# Power_supply_dual_-_2_5_V_250_mA_-_TI_LM.net
KiCad netlist of a schematic drawn in Altium Designer
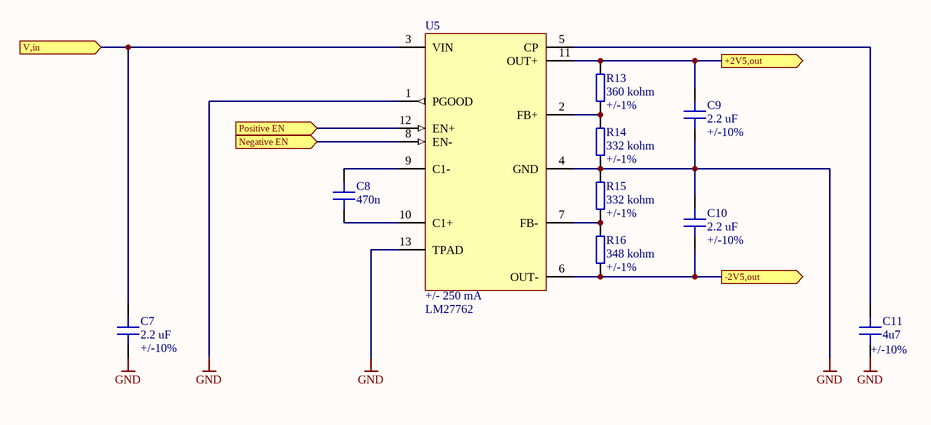
[diagram p0: Power supply, dual - 2.5 V 250 mA - TI LM27762.SchDoc]

(export (version "E")
  (design (tool "Eeschema 10.0.6"))
  (components
    (comp (ref "C7")
      (value "2.2 uF")
      (footprint "Capacitor 0805 [2012 Metric]; SMT")
      (fields
        (field (name "TOLERANCE") "+/-10%")
        (field (name "PART NUMBER") "GRM21BR61H225KA73L")
        (field (name "Comment") "Capacitor")
        (field (name "AUTHOR") "Jeroen de Bruijn")
      )
      (libsource (lib "VidavidorraDb") (part "Capacitor"))
    )
    (comp (ref "C8")
      (value "470n")
      (footprint "Capacitor 0805 [2012 Metric]; SMT")
      (fields (field (name "Comment") "Capacitor") (field (name "AUTHOR") "Jeroen de Bruijn"))
      (libsource (lib "VidavidorraDb") (part "Capacitor"))
    )
    (comp (ref "C9")
      (value "2.2 uF")
      (footprint "Capacitor 0805 [2012 Metric]; SMT")
      (fields
        (field (name "TOLERANCE") "+/-10%")
        (field (name "PART NUMBER") "GRM21BR61H225KA73L")
        (field (name "Comment") "Capacitor")
        (field (name "AUTHOR") "Jeroen de Bruijn")
      )
      (libsource (lib "VidavidorraDb") (part "Capacitor"))
    )
    (comp (ref "C10")
      (value "2.2 uF")
      (footprint "Capacitor 0805 [2012 Metric]; SMT")
      (fields
        (field (name "TOLERANCE") "+/-10%")
        (field (name "PART NUMBER") "GRM21BR61H225KA73L")
        (field (name "Comment") "Capacitor")
        (field (name "AUTHOR") "Jeroen de Bruijn")
      )
      (libsource (lib "VidavidorraDb") (part "Capacitor"))
    )
    (comp (ref "C11")
      (value "4u7")
      (footprint "Capacitor 0805 [2012 Metric]; SMT")
      (fields
        (field (name "TOLERANCE") "+/-10%")
        (field (name "PART NUMBER") "0805B475K160CT")
        (field (name "Comment") "Capacitor")
        (field (name "AUTHOR") "Jeroen de Bruijn")
      )
      (libsource (lib "VidavidorraDb") (part "Capacitor"))
    )
    (comp (ref "R13")
      (value "360 kohm")
      (footprint "Resistor 0805 [2012 Metric]; SMT")
      (fields
        (field (name "TOLERANCE") "+/-1%")
        (field (name "PART NUMBER") "MC01W08051360K")
        (field (name "Comment") "Resistor")
        (field (name "AUTHOR") "Jeroen de Bruijn")
      )
      (libsource (lib "VidavidorraDb") (part "Resistor"))
    )
    (comp (ref "R14")
      (value "332 kohm")
      (footprint "Resistor 0805 [2012 Metric]; SMT")
      (fields
        (field (name "TOLERANCE") "+/-1%")
        (field (name "PART NUMBER") "MC01W08051332K")
        (field (name "Comment") "Resistor")
        (field (name "AUTHOR") "Jeroen de Bruijn")
      )
      (libsource (lib "VidavidorraDb") (part "Resistor"))
    )
    (comp (ref "R15")
      (value "332 kohm")
      (footprint "Resistor 0805 [2012 Metric]; SMT")
      (fields
        (field (name "TOLERANCE") "+/-1%")
        (field (name "PART NUMBER") "MC01W08051332K")
        (field (name "Comment") "Resistor")
        (field (name "AUTHOR") "Jeroen de Bruijn")
      )
      (libsource (lib "VidavidorraDb") (part "Resistor"))
    )
    (comp (ref "R16")
      (value "348 kohm")
      (footprint "Resistor 0805 [2012 Metric]; SMT")
      (fields
        (field (name "TOLERANCE") "+/-1%")
        (field (name "PART NUMBER") "MC01W08051348K")
        (field (name "Comment") "Resistor")
        (field (name "AUTHOR") "Jeroen de Bruijn")
      )
      (libsource (lib "VidavidorraDb") (part "Resistor"))
    )
    (comp (ref "U5")
      (value "TI LM27762")
      (footprint "R-PWSON-N12")
      (fields
        (field (name "OUTPUT CURRENT") "+/- 250 mA")
        (field (name "PART NUMBER") "LM27762")
        (field (name "MANUFACTURER 1 PART NO") "LM27762")
        (field (name "AUTHOR") "Jeroen de Bruijn")
      )
      (libsource (lib "VidavidorraDb") (part "TI LM27762"))
    )
  )
  (nets
    (net (code "1") (name "/+2V5,out") (class "Default")
      (node (ref "C9") (pin "1") (pinfunction "1_1") (pintype "passive"))
      (node (ref "R13") (pin "1") (pinfunction "1_1") (pintype "passive"))
      (node (ref "U5") (pin "11") (pinfunction "OUT+_11") (pintype "power_in"))
    )
    (net (code "2") (name "/-2V5,out") (class "Default")
      (node (ref "C10") (pin "0") (pinfunction "0_0") (pintype "passive"))
      (node (ref "R16") (pin "0") (pinfunction "0_0") (pintype "passive"))
      (node (ref "U5") (pin "6") (pinfunction "OUT-_6") (pintype "power_in"))
    )
    (net (code "3") (name "/Negative EN") (class "Default")
      (node (ref "U5") (pin "8") (pinfunction "EN-_8") (pintype "input"))
    )
    (net (code "4") (name "/Positive EN") (class "Default")
      (node (ref "U5") (pin "12") (pinfunction "EN+_12") (pintype "input"))
    )
    (net (code "5") (name "/V,in") (class "Default")
      (node (ref "C7") (pin "1") (pinfunction "1_1") (pintype "passive"))
      (node (ref "U5") (pin "3") (pinfunction "VIN_3") (pintype "power_in"))
    )
    (net (code "6") (name "GND") (class "Default")
      (node (ref "C10") (pin "1") (pinfunction "1_1") (pintype "passive"))
      (node (ref "C11") (pin "0") (pinfunction "0_0") (pintype "passive"))
      (node (ref "C7") (pin "0") (pinfunction "0_0") (pintype "passive"))
      (node (ref "C9") (pin "0") (pinfunction "0_0") (pintype "passive"))
      (node (ref "R14") (pin "0") (pinfunction "0_0") (pintype "passive"))
      (node (ref "R15") (pin "1") (pinfunction "1_1") (pintype "passive"))
      (node (ref "U5") (pin "1") (pinfunction "PGOOD_1") (pintype "output"))
      (node (ref "U5") (pin "13") (pinfunction "TPAD_13") (pintype "power_in"))
      (node (ref "U5") (pin "4") (pinfunction "GND_4") (pintype "power_in"))
    )
    (net (code "7") (name "Net-(U5-C1+)") (class "Default")
      (node (ref "C8") (pin "0") (pinfunction "0_0") (pintype "passive"))
      (node (ref "U5") (pin "10") (pinfunction "C1+_10") (pintype "passive"))
    )
    (net (code "8") (name "Net-(U5-C1-)") (class "Default")
      (node (ref "C8") (pin "1") (pinfunction "1_1") (pintype "passive"))
      (node (ref "U5") (pin "9") (pinfunction "C1-_9") (pintype "passive"))
    )
    (net (code "9") (name "Net-(U5-CP)") (class "Default")
      (node (ref "C11") (pin "1") (pinfunction "1_1") (pintype "passive"))
      (node (ref "U5") (pin "5") (pinfunction "CP_5") (pintype "power_in"))
    )
    (net (code "10") (name "Net-(U5-FB+)") (class "Default")
      (node (ref "R13") (pin "0") (pinfunction "0_0") (pintype "passive"))
      (node (ref "R14") (pin "1") (pinfunction "1_1") (pintype "passive"))
      (node (ref "U5") (pin "2") (pinfunction "FB+_2") (pintype "power_in"))
    )
    (net (code "11") (name "Net-(U5-FB-)") (class "Default")
      (node (ref "R15") (pin "0") (pinfunction "0_0") (pintype "passive"))
      (node (ref "R16") (pin "1") (pinfunction "1_1") (pintype "passive"))
      (node (ref "U5") (pin "7") (pinfunction "FB-_7") (pintype "power_in"))
    )
  )
)
